# Netzteil_15V.net
KiCad netlist of a schematic drawn in EAGLE
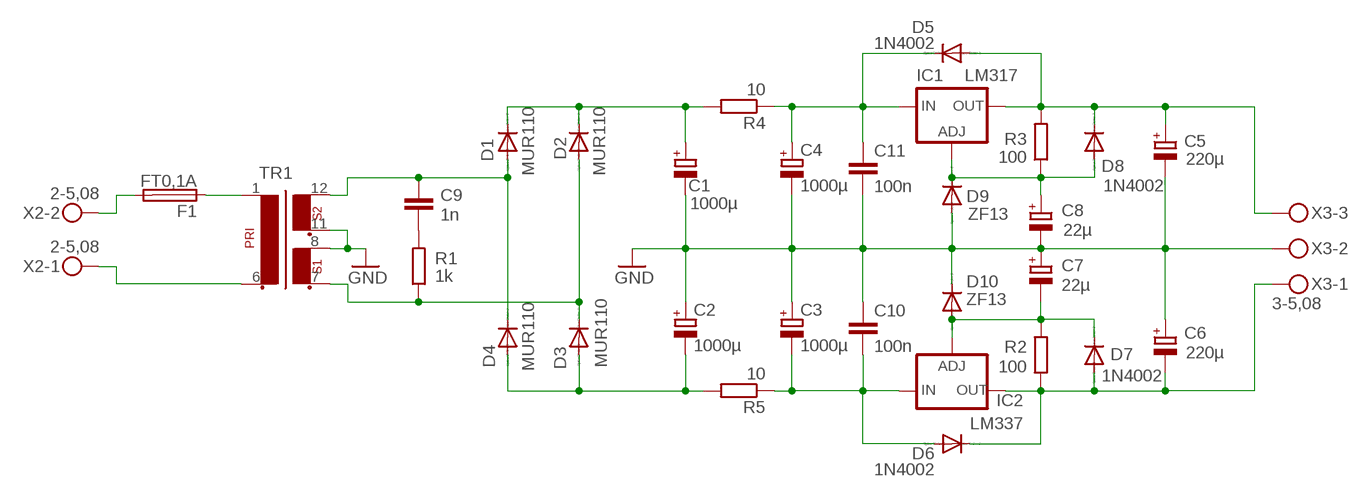
[diagram p0: schematic, sheet 1]

(export (version "E")
  (design (tool "Eeschema 10.0.6"))
  (components
    (comp (ref "C1")
      (value "1000µ")
      (footprint "eagle-import:E5-13")
      (libsource (lib "eagle-import") (part "CPOL-EUE5-13"))
    )
    (comp (ref "C2")
      (value "1000µ")
      (footprint "eagle-import:E5-13")
      (libsource (lib "eagle-import") (part "CPOL-EUE5-13"))
    )
    (comp (ref "C3")
      (value "1000µ")
      (footprint "eagle-import:E5-13")
      (libsource (lib "eagle-import") (part "CPOL-EUE5-13"))
    )
    (comp (ref "C4")
      (value "1000µ")
      (footprint "eagle-import:E5-13")
      (libsource (lib "eagle-import") (part "CPOL-EUE5-13"))
    )
    (comp (ref "C5")
      (value "220µ")
      (footprint "eagle-import:E3,5-8")
      (libsource (lib "eagle-import") (part "CPOL-EUE3.5-8"))
    )
    (comp (ref "C6")
      (value "220µ")
      (footprint "eagle-import:E3,5-8")
      (libsource (lib "eagle-import") (part "CPOL-EUE3.5-8"))
    )
    (comp (ref "C7")
      (value "22µ")
      (footprint "eagle-import:E2-5")
      (libsource (lib "eagle-import") (part "CPOL-EUE2-5"))
    )
    (comp (ref "C8")
      (value "22µ")
      (footprint "eagle-import:E2-5")
      (libsource (lib "eagle-import") (part "CPOL-EUE2-5"))
    )
    (comp (ref "C9")
      (value "1n")
      (footprint "eagle-import:C050-045X075")
      (libsource (lib "eagle-import") (part "C-EU050-045X075"))
    )
    (comp (ref "C10")
      (value "100n")
      (footprint "eagle-import:C050-025X075")
      (libsource (lib "eagle-import") (part "C-EU050-025X075"))
    )
    (comp (ref "C11")
      (value "100n")
      (footprint "eagle-import:C050-025X075")
      (libsource (lib "eagle-import") (part "C-EU050-025X075"))
    )
    (comp (ref "D1")
      (value "MUR110")
      (footprint "eagle-import:DO41-10")
      (libsource (lib "eagle-import") (part "MUR150RL"))
    )
    (comp (ref "D2")
      (value "MUR110")
      (footprint "eagle-import:DO41-10")
      (libsource (lib "eagle-import") (part "MUR150RL"))
    )
    (comp (ref "D3")
      (value "MUR110")
      (footprint "eagle-import:DO41-10")
      (libsource (lib "eagle-import") (part "MUR150RL"))
    )
    (comp (ref "D4")
      (value "MUR110")
      (footprint "eagle-import:DO41-10")
      (libsource (lib "eagle-import") (part "MUR150RL"))
    )
    (comp (ref "D5")
      (value "1N4002")
      (footprint "eagle-import:DO41-10")
      (libsource (lib "eagle-import") (part "MUR150RL"))
    )
    (comp (ref "D6")
      (value "1N4002")
      (footprint "eagle-import:DO41-10")
      (libsource (lib "eagle-import") (part "MUR150RL"))
    )
    (comp (ref "D7")
      (value "1N4002")
      (footprint "eagle-import:DO41-10")
      (libsource (lib "eagle-import") (part "MUR150RL"))
    )
    (comp (ref "D8")
      (value "1N4002")
      (footprint "eagle-import:DO41-10")
      (libsource (lib "eagle-import") (part "MUR150RL"))
    )
    (comp (ref "D9")
      (value "ZF13")
      (footprint "eagle-import:DO35-7")
      (libsource (lib "eagle-import") (part "1N4148DO35-7"))
    )
    (comp (ref "D10")
      (value "ZF13")
      (footprint "eagle-import:DO35-7")
      (libsource (lib "eagle-import") (part "1N4148DO35-7"))
    )
    (comp (ref "F1")
      (value "FT0,1A")
      (footprint "eagle-import:19560")
      (fields (field (name "MPN") "56000001009"))
      (libsource (lib "eagle-import") (part "FUSE19560"))
    )
    (comp (ref "IC1")
      (value "LM317")
      (footprint "eagle-import:317TS")
      (libsource (lib "eagle-import") (part "LM317TS"))
    )
    (comp (ref "IC2")
      (value "LM337")
      (footprint "eagle-import:337TS")
      (libsource (lib "eagle-import") (part "LM337TS"))
    )
    (comp (ref "R1")
      (value "1k")
      (footprint "eagle-import:0207_10")
      (libsource (lib "eagle-import") (part "R-EU_0207/10"))
    )
    (comp (ref "R2")
      (value "100")
      (footprint "eagle-import:0207_10")
      (libsource (lib "eagle-import") (part "R-EU_0207/10"))
    )
    (comp (ref "R3")
      (value "100")
      (footprint "eagle-import:0207_10")
      (libsource (lib "eagle-import") (part "R-EU_0207/10"))
    )
    (comp (ref "R4")
      (value "10")
      (footprint "eagle-import:0617V")
      (libsource (lib "eagle-import") (part "R-EU_0617/5V"))
    )
    (comp (ref "R5")
      (value "10")
      (footprint "eagle-import:0617V")
      (libsource (lib "eagle-import") (part "R-EU_0617/5V"))
    )
    (comp (ref "TR1")
      (value "EI48-2")
      (footprint "eagle-import:EI48-2")
      (libsource (lib "eagle-import") (part "EI48-2"))
    )
    (comp (ref "X2")
      (value "2-5,08")
      (footprint "eagle-import:MKDSN1,5_2-5,08")
      (libsource (lib "eagle-import") (part "MKDSN1,5/2-5,08"))
    )
    (comp (ref "X3")
      (value "3-5,08")
      (footprint "eagle-import:MKDSN1,5_3-5,08")
      (libsource (lib "eagle-import") (part "MKDSN1,5/3-5,08"))
    )
  )
  (nets
    (net (code "1") (name "GND") (class "Default")
      (node (ref "C1") (pin "-") (pinfunction "-_-") (pintype "passive"))
      (node (ref "C10") (pin "1") (pinfunction "1_1") (pintype "passive"))
      (node (ref "C11") (pin "2") (pinfunction "2_2") (pintype "passive"))
      (node (ref "C2") (pin "+") (pinfunction "+_+") (pintype "passive"))
      (node (ref "C3") (pin "+") (pinfunction "+_+") (pintype "passive"))
      (node (ref "C4") (pin "-") (pinfunction "-_-") (pintype "passive"))
      (node (ref "C5") (pin "-") (pinfunction "-_-") (pintype "passive"))
      (node (ref "C6") (pin "+") (pinfunction "+_+") (pintype "passive"))
      (node (ref "C7") (pin "+") (pinfunction "+_+") (pintype "passive"))
      (node (ref "C8") (pin "-") (pinfunction "-_-") (pintype "passive"))
      (node (ref "D10") (pin "C") (pinfunction "C_C") (pintype "passive"))
      (node (ref "D9") (pin "A") (pinfunction "A_A") (pintype "passive"))
      (node (ref "TR1") (pin "11") (pinfunction "5_11") (pintype "passive"))
      (node (ref "TR1") (pin "8") (pinfunction "4_8") (pintype "passive"))
      (node (ref "X3") (pin "2") (pinfunction "KL_2") (pintype "passive"))
    )
    (net (code "2") (name "Net-(C1-Pad+)") (class "Default")
      (node (ref "C1") (pin "+") (pinfunction "+_+") (pintype "passive"))
      (node (ref "D1") (pin "C") (pinfunction "C_C") (pintype "passive"))
      (node (ref "D2") (pin "C") (pinfunction "C_C") (pintype "passive"))
      (node (ref "R4") (pin "2") (pinfunction "2_2") (pintype "passive"))
    )
    (net (code "3") (name "Net-(C2-Pad-)") (class "Default")
      (node (ref "C2") (pin "-") (pinfunction "-_-") (pintype "passive"))
      (node (ref "D3") (pin "A") (pinfunction "A_A") (pintype "passive"))
      (node (ref "D4") (pin "A") (pinfunction "A_A") (pintype "passive"))
      (node (ref "R5") (pin "2") (pinfunction "2_2") (pintype "passive"))
    )
    (net (code "4") (name "Net-(C9-Pad2)") (class "Default")
      (node (ref "C9") (pin "2") (pinfunction "2_2") (pintype "passive"))
      (node (ref "R1") (pin "2") (pinfunction "2_2") (pintype "passive"))
    )
    (net (code "5") (name "Net-(F1-Pad1)") (class "Default")
      (node (ref "F1") (pin "1") (pinfunction "1_1") (pintype "passive"))
      (node (ref "TR1") (pin "1") (pinfunction "1_1") (pintype "passive"))
    )
    (net (code "6") (name "Net-(IC1-ADJ)") (class "Default")
      (node (ref "C8") (pin "+") (pinfunction "+_+") (pintype "passive"))
      (node (ref "D8") (pin "A") (pinfunction "A_A") (pintype "passive"))
      (node (ref "D9") (pin "C") (pinfunction "C_C") (pintype "passive"))
      (node (ref "IC1") (pin "1") (pinfunction "ADJ_1") (pintype "input"))
      (node (ref "R3") (pin "1") (pinfunction "1_1") (pintype "passive"))
    )
    (net (code "7") (name "Net-(IC1-IN)") (class "Default")
      (node (ref "C11") (pin "1") (pinfunction "1_1") (pintype "passive"))
      (node (ref "C4") (pin "+") (pinfunction "+_+") (pintype "passive"))
      (node (ref "D5") (pin "C") (pinfunction "C_C") (pintype "passive"))
      (node (ref "IC1") (pin "3") (pinfunction "IN_3") (pintype "input"))
      (node (ref "R4") (pin "1") (pinfunction "1_1") (pintype "passive"))
    )
    (net (code "8") (name "Net-(IC1-OUT)") (class "Default")
      (node (ref "C5") (pin "+") (pinfunction "+_+") (pintype "passive"))
      (node (ref "D5") (pin "A") (pinfunction "A_A") (pintype "passive"))
      (node (ref "D8") (pin "C") (pinfunction "C_C") (pintype "passive"))
      (node (ref "IC1") (pin "2") (pinfunction "OUT_2") (pintype "passive"))
      (node (ref "R3") (pin "2") (pinfunction "2_2") (pintype "passive"))
      (node (ref "X3") (pin "3") (pinfunction "KL_3") (pintype "passive"))
    )
    (net (code "9") (name "Net-(IC2-ADJ)") (class "Default")
      (node (ref "C7") (pin "-") (pinfunction "-_-") (pintype "passive"))
      (node (ref "D10") (pin "A") (pinfunction "A_A") (pintype "passive"))
      (node (ref "D7") (pin "C") (pinfunction "C_C") (pintype "passive"))
      (node (ref "IC2") (pin "1") (pinfunction "ADJ_1") (pintype "input"))
      (node (ref "R2") (pin "2") (pinfunction "2_2") (pintype "passive"))
    )
    (net (code "10") (name "Net-(IC2-IN)") (class "Default")
      (node (ref "C10") (pin "2") (pinfunction "2_2") (pintype "passive"))
      (node (ref "C3") (pin "-") (pinfunction "-_-") (pintype "passive"))
      (node (ref "D6") (pin "A") (pinfunction "A_A") (pintype "passive"))
      (node (ref "IC2") (pin "2") (pinfunction "IN_2") (pintype "input"))
      (node (ref "R5") (pin "1") (pinfunction "1_1") (pintype "passive"))
    )
    (net (code "11") (name "Net-(IC2-OUT)") (class "Default")
      (node (ref "C6") (pin "-") (pinfunction "-_-") (pintype "passive"))
      (node (ref "D6") (pin "C") (pinfunction "C_C") (pintype "passive"))
      (node (ref "D7") (pin "A") (pinfunction "A_A") (pintype "passive"))
      (node (ref "IC2") (pin "3") (pinfunction "OUT_3") (pintype "passive"))
      (node (ref "R2") (pin "1") (pinfunction "1_1") (pintype "passive"))
      (node (ref "X3") (pin "1") (pinfunction "KL_1") (pintype "passive"))
    )
    (net (code "12") (name "Net-(TR1-2)") (class "Default")
      (node (ref "TR1") (pin "6") (pinfunction "2_6") (pintype "passive"))
      (node (ref "X2") (pin "1") (pinfunction "KL_1") (pintype "passive"))
    )
    (net (code "13") (name "Net-(TR1-3)") (class "Default")
      (node (ref "D2") (pin "A") (pinfunction "A_A") (pintype "passive"))
      (node (ref "D3") (pin "C") (pinfunction "C_C") (pintype "passive"))
      (node (ref "R1") (pin "1") (pinfunction "1_1") (pintype "passive"))
      (node (ref "TR1") (pin "7") (pinfunction "3_7") (pintype "passive"))
    )
    (net (code "14") (name "Net-(TR1-6)") (class "Default")
      (node (ref "C9") (pin "1") (pinfunction "1_1") (pintype "passive"))
      (node (ref "D1") (pin "A") (pinfunction "A_A") (pintype "passive"))
      (node (ref "D4") (pin "C") (pinfunction "C_C") (pintype "passive"))
      (node (ref "TR1") (pin "12") (pinfunction "6_12") (pintype "passive"))
    )
    (net (code "15") (name "Net-(X2B-KL)") (class "Default")
      (node (ref "F1") (pin "2") (pinfunction "2_2") (pintype "passive"))
      (node (ref "X2") (pin "2") (pinfunction "KL_2") (pintype "passive"))
    )
  )
)
